# RGB-VIDEO.net
KiCad netlist of a schematic drawn in EAGLE
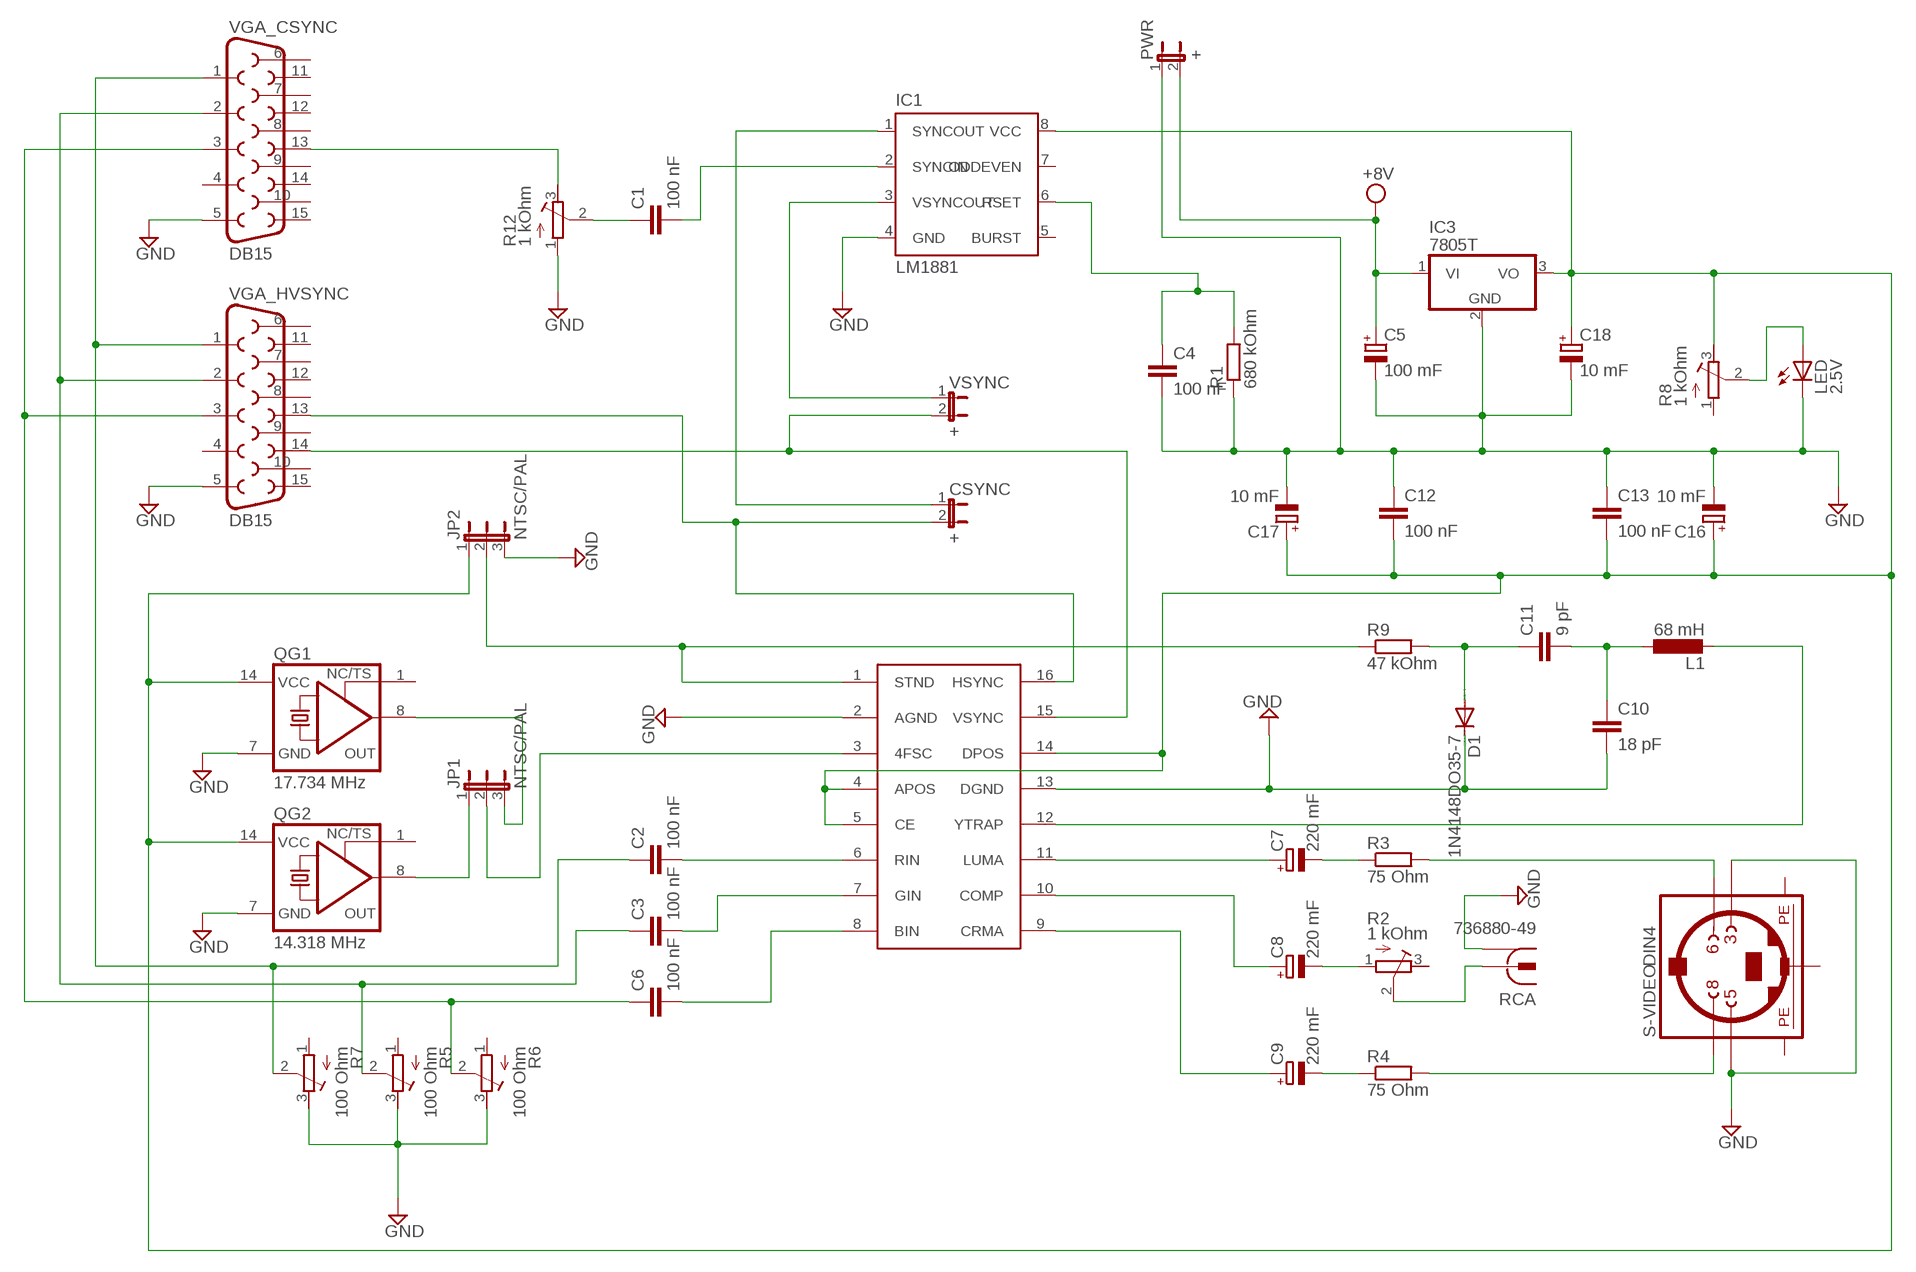
[diagram p0: schematic, sheet 1]

(export (version "E")
  (design (tool "Eeschema 10.0.6"))
  (components
    (comp (ref "C1")
      (value "100 nF")
      (footprint "eagle-import:C050-025X075")
      (libsource (lib "eagle-import") (part "C-EU050-025X075"))
    )
    (comp (ref "C2")
      (value "100 nF")
      (footprint "eagle-import:C050-025X075")
      (libsource (lib "eagle-import") (part "C-EU050-025X075"))
    )
    (comp (ref "C3")
      (value "100 nF")
      (footprint "eagle-import:C050-025X075")
      (libsource (lib "eagle-import") (part "C-EU050-025X075"))
    )
    (comp (ref "C4")
      (value "100 nF")
      (footprint "eagle-import:C050-025X075")
      (libsource (lib "eagle-import") (part "C-EU050-025X075"))
    )
    (comp (ref "C5")
      (value "100 mF")
      (footprint "eagle-import:E3,5-10")
      (libsource (lib "eagle-import") (part "CPOL-EUE3.5-10"))
    )
    (comp (ref "C6")
      (value "100 nF")
      (footprint "eagle-import:C050-025X075")
      (libsource (lib "eagle-import") (part "C-EU050-025X075"))
    )
    (comp (ref "C7")
      (value "220 mF")
      (footprint "eagle-import:E3,5-10")
      (libsource (lib "eagle-import") (part "CPOL-EUE3.5-10"))
    )
    (comp (ref "C8")
      (value "220 mF")
      (footprint "eagle-import:E3,5-10")
      (libsource (lib "eagle-import") (part "CPOL-EUE3.5-10"))
    )
    (comp (ref "C9")
      (value "220 mF")
      (footprint "eagle-import:E3,5-10")
      (libsource (lib "eagle-import") (part "CPOL-EUE3.5-10"))
    )
    (comp (ref "C10")
      (value "18 pF")
      (footprint "eagle-import:C025-024X044")
      (libsource (lib "eagle-import") (part "C-EU025-024X044"))
    )
    (comp (ref "C11")
      (value "9 pF")
      (footprint "eagle-import:C025-024X044")
      (libsource (lib "eagle-import") (part "C-EU025-024X044"))
    )
    (comp (ref "C12")
      (value "100 nF")
      (footprint "eagle-import:C050-025X075")
      (libsource (lib "eagle-import") (part "C-EU050-025X075"))
    )
    (comp (ref "C13")
      (value "100 nF")
      (footprint "eagle-import:C050-025X075")
      (libsource (lib "eagle-import") (part "C-EU050-025X075"))
    )
    (comp (ref "C16")
      (value "10 mF")
      (footprint "eagle-import:E3,5-8")
      (libsource (lib "eagle-import") (part "CPOL-EUE3.5-8"))
    )
    (comp (ref "C17")
      (value "10 mF")
      (footprint "eagle-import:E3,5-8")
      (libsource (lib "eagle-import") (part "CPOL-EUE3.5-8"))
    )
    (comp (ref "C18")
      (value "10 mF")
      (footprint "eagle-import:E3,5-8")
      (libsource (lib "eagle-import") (part "CPOL-EUE3.5-8"))
    )
    (comp (ref "CSYNC")
      (value "+")
      (footprint "eagle-import:JP1")
      (libsource (lib "eagle-import") (part "JP1E"))
    )
    (comp (ref "D1")
      (value "1N4148DO35-7")
      (footprint "eagle-import:DO35-7")
      (libsource (lib "eagle-import") (part "1N4148DO35-7"))
    )
    (comp (ref "IC1")
      (value "LM1881")
      (footprint "eagle-import:DIL08")
      (libsource (lib "eagle-import") (part "LM1881"))
    )
    (comp (ref "IC2")
      (value "AD725")
      (footprint "eagle-import:SO16W")
      (libsource (lib "eagle-import") (part "AD725"))
    )
    (comp (ref "IC3")
      (value "7805T")
      (footprint "eagle-import:TO220H")
      (libsource (lib "eagle-import") (part "78T05"))
    )
    (comp (ref "JP1")
      (value "NTSC/PAL")
      (footprint "eagle-import:JP2")
      (libsource (lib "eagle-import") (part "JP2E"))
    )
    (comp (ref "JP2")
      (value "NTSC/PAL")
      (footprint "eagle-import:JP2")
      (libsource (lib "eagle-import") (part "JP2E"))
    )
    (comp (ref "L1")
      (value "68 mH")
      (footprint "eagle-import:6000-XXXX-RC")
      (libsource (lib "eagle-import") (part "L-EU6000-XXX-RC"))
    )
    (comp (ref "LED")
      (value "2.5V")
      (footprint "eagle-import:LED3MM")
      (libsource (lib "eagle-import") (part "LED3MM"))
    )
    (comp (ref "PWR")
      (value "+")
      (footprint "eagle-import:JP1")
      (libsource (lib "eagle-import") (part "JP1E"))
    )
    (comp (ref "QG1")
      (value "17.734 MHz")
      (footprint "eagle-import:DIL14S")
      (libsource (lib "eagle-import") (part "XO-14"))
    )
    (comp (ref "QG2")
      (value "14.318 MHz")
      (footprint "eagle-import:DIL14S")
      (libsource (lib "eagle-import") (part "XO-14"))
    )
    (comp (ref "R1")
      (value "680 kOhm")
      (footprint "eagle-import:0204_7")
      (libsource (lib "eagle-import") (part "R-EU_0204/7"))
    )
    (comp (ref "R2")
      (value "1 kOhm")
      (footprint "eagle-import:RTRIM3339P")
      (libsource (lib "eagle-import") (part "R-TRIMM3339P"))
    )
    (comp (ref "R3")
      (value "75 Ohm")
      (footprint "eagle-import:0204_7")
      (libsource (lib "eagle-import") (part "R-EU_0204/7"))
    )
    (comp (ref "R4")
      (value "75 Ohm")
      (footprint "eagle-import:0204_7")
      (libsource (lib "eagle-import") (part "R-EU_0204/7"))
    )
    (comp (ref "R5")
      (value "100 Ohm")
      (footprint "eagle-import:RTRIM3339P")
      (libsource (lib "eagle-import") (part "R-TRIMM3339P"))
    )
    (comp (ref "R6")
      (value "100 Ohm")
      (footprint "eagle-import:RTRIM3339P")
      (libsource (lib "eagle-import") (part "R-TRIMM3339P"))
    )
    (comp (ref "R7")
      (value "100 Ohm")
      (footprint "eagle-import:RTRIM3339P")
      (libsource (lib "eagle-import") (part "R-TRIMM3339P"))
    )
    (comp (ref "R8")
      (value "1 kOhm")
      (footprint "eagle-import:RTRIM3339P")
      (libsource (lib "eagle-import") (part "R-TRIMM3339P"))
    )
    (comp (ref "R9")
      (value "47 kOhm")
      (footprint "eagle-import:0204_7")
      (libsource (lib "eagle-import") (part "R-EU_0204/7"))
    )
    (comp (ref "R12")
      (value "1 kOhm")
      (footprint "eagle-import:RTRIM3339P")
      (libsource (lib "eagle-import") (part "R-TRIMM3339P"))
    )
    (comp (ref "RCA")
      (value "736880-49")
      (footprint "eagle-import:736880-49")
      (libsource (lib "eagle-import") (part "736880-49"))
    )
    (comp (ref "S-VIDEO")
      (value "DIN4")
      (footprint "eagle-import:M_DIN4")
      (libsource (lib "eagle-import") (part "MINI_DIN_4"))
    )
    (comp (ref "VGA_CSYNC")
      (value "DB15")
      (footprint "eagle-import:DB15")
      (libsource (lib "eagle-import") (part "DB15"))
    )
    (comp (ref "VGA_HVSYNC")
      (value "DB15")
      (footprint "eagle-import:DB15")
      (libsource (lib "eagle-import") (part "DB15"))
    )
    (comp (ref "VSYNC")
      (value "+")
      (footprint "eagle-import:JP1")
      (libsource (lib "eagle-import") (part "JP1E"))
    )
  )
  (nets
    (net (code "1") (name "+8V") (class "Default")
      (node (ref "C5") (pin "+") (pinfunction "+_+") (pintype "passive"))
      (node (ref "IC3") (pin "1") (pinfunction "VI_1") (pintype "input"))
      (node (ref "PWR") (pin "2") (pinfunction "2_2") (pintype "passive"))
    )
    (net (code "2") (name "/PE1") (class "Default")
      (node (ref "S-VIDEO") (pin "SH1") (pinfunction "PE1_SH1") (pintype "power_in"))
    )
    (net (code "3") (name "/PE2") (class "Default")
      (node (ref "S-VIDEO") (pin "SH2") (pinfunction "PE2_SH2") (pintype "power_in"))
    )
    (net (code "4") (name "/PE3") (class "Default")
      (node (ref "S-VIDEO") (pin "SH3") (pinfunction "PE3_SH3") (pintype "power_in"))
    )
    (net (code "5") (name "GND") (class "Default")
      (node (ref "C10") (pin "2") (pinfunction "2_2") (pintype "passive"))
      (node (ref "C12") (pin "1") (pinfunction "1_1") (pintype "passive"))
      (node (ref "C13") (pin "1") (pinfunction "1_1") (pintype "passive"))
      (node (ref "C16") (pin "-") (pinfunction "-_-") (pintype "passive"))
      (node (ref "C17") (pin "-") (pinfunction "-_-") (pintype "passive"))
      (node (ref "C18") (pin "-") (pinfunction "-_-") (pintype "passive"))
      (node (ref "C4") (pin "2") (pinfunction "2_2") (pintype "passive"))
      (node (ref "C5") (pin "-") (pinfunction "-_-") (pintype "passive"))
      (node (ref "D1") (pin "C") (pinfunction "C_C") (pintype "passive"))
      (node (ref "IC1") (pin "4") (pinfunction "GND_4") (pintype "power_in"))
      (node (ref "IC2") (pin "13") (pinfunction "DGND_13") (pintype "bidirectional"))
      (node (ref "IC2") (pin "2") (pinfunction "AGND_2") (pintype "bidirectional"))
      (node (ref "IC3") (pin "2") (pinfunction "GND_2") (pintype "passive"))
      (node (ref "JP2") (pin "3") (pinfunction "3_3") (pintype "passive"))
      (node (ref "LED") (pin "K") (pinfunction "C_K") (pintype "passive"))
      (node (ref "PWR") (pin "1") (pinfunction "1_1") (pintype "passive"))
      (node (ref "QG1") (pin "7") (pinfunction "GND_7") (pintype "power_in"))
      (node (ref "QG2") (pin "7") (pinfunction "GND_7") (pintype "power_in"))
      (node (ref "R1") (pin "1") (pinfunction "1_1") (pintype "passive"))
      (node (ref "R12") (pin "1") (pinfunction "A_1") (pintype "passive"))
      (node (ref "R5") (pin "3") (pinfunction "E_3") (pintype "passive"))
      (node (ref "R6") (pin "3") (pinfunction "E_3") (pintype "passive"))
      (node (ref "R7") (pin "3") (pinfunction "E_3") (pintype "passive"))
      (node (ref "RCA") (pin "1") (pinfunction "1_1") (pintype "passive"))
      (node (ref "RCA") (pin "1@1") (pinfunction "1_1@1") (pintype "passive"))
      (node (ref "RCA") (pin "1@2") (pinfunction "1_1@2") (pintype "passive"))
      (node (ref "S-VIDEO") (pin "3") (pinfunction "3_3") (pintype "passive"))
      (node (ref "S-VIDEO") (pin "5") (pinfunction "5_5") (pintype "passive"))
      (node (ref "VGA_CSYNC") (pin "5") (pinfunction "5_5") (pintype "passive"))
      (node (ref "VGA_HVSYNC") (pin "5") (pinfunction "5_5") (pintype "passive"))
    )
    (net (code "6") (name "Net-(C7-Pad-)") (class "Default")
      (node (ref "C7") (pin "-") (pinfunction "-_-") (pintype "passive"))
      (node (ref "R3") (pin "1") (pinfunction "1_1") (pintype "passive"))
    )
    (net (code "7") (name "Net-(C9-Pad-)") (class "Default")
      (node (ref "C9") (pin "-") (pinfunction "-_-") (pintype "passive"))
      (node (ref "R4") (pin "1") (pinfunction "1_1") (pintype "passive"))
    )
    (net (code "8") (name "Net-(C10-Pad1)") (class "Default")
      (node (ref "C10") (pin "1") (pinfunction "1_1") (pintype "passive"))
      (node (ref "C11") (pin "2") (pinfunction "2_2") (pintype "passive"))
      (node (ref "L1") (pin "1") (pinfunction "1_1") (pintype "passive"))
    )
    (net (code "9") (name "Net-(C11-Pad1)") (class "Default")
      (node (ref "C11") (pin "1") (pinfunction "1_1") (pintype "passive"))
      (node (ref "D1") (pin "A") (pinfunction "A_A") (pintype "passive"))
      (node (ref "R9") (pin "2") (pinfunction "2_2") (pintype "passive"))
    )
    (net (code "10") (name "Net-(IC1-RSET)") (class "Default")
      (node (ref "C4") (pin "1") (pinfunction "1_1") (pintype "passive"))
      (node (ref "IC1") (pin "6") (pinfunction "RSET_6") (pintype "output"))
      (node (ref "R1") (pin "2") (pinfunction "2_2") (pintype "passive"))
    )
    (net (code "11") (name "Net-(IC1-SYNCIN)") (class "Default")
      (node (ref "C1") (pin "2") (pinfunction "2_2") (pintype "passive"))
      (node (ref "IC1") (pin "2") (pinfunction "SYNCIN_2") (pintype "input"))
    )
    (net (code "12") (name "Net-(IC1-SYNCOUT)") (class "Default")
      (node (ref "CSYNC") (pin "1") (pinfunction "1_1") (pintype "passive"))
      (node (ref "IC1") (pin "1") (pinfunction "SYNCOUT_1") (pintype "output"))
    )
    (net (code "13") (name "Net-(IC1-VCC)") (class "Default")
      (node (ref "C12") (pin "2") (pinfunction "2_2") (pintype "passive"))
      (node (ref "C13") (pin "2") (pinfunction "2_2") (pintype "passive"))
      (node (ref "C16") (pin "+") (pinfunction "+_+") (pintype "passive"))
      (node (ref "C17") (pin "+") (pinfunction "+_+") (pintype "passive"))
      (node (ref "C18") (pin "+") (pinfunction "+_+") (pintype "passive"))
      (node (ref "IC1") (pin "8") (pinfunction "VCC_8") (pintype "power_in"))
      (node (ref "IC2") (pin "14") (pinfunction "DPOS_14") (pintype "bidirectional"))
      (node (ref "IC2") (pin "4") (pinfunction "APOS_4") (pintype "bidirectional"))
      (node (ref "IC2") (pin "5") (pinfunction "CE_5") (pintype "bidirectional"))
      (node (ref "IC3") (pin "3") (pinfunction "VO_3") (pintype "passive"))
      (node (ref "JP2") (pin "1") (pinfunction "1_1") (pintype "passive"))
      (node (ref "QG1") (pin "14") (pinfunction "VCC_14") (pintype "power_in"))
      (node (ref "QG2") (pin "14") (pinfunction "VCC_14") (pintype "power_in"))
      (node (ref "R8") (pin "3") (pinfunction "E_3") (pintype "passive"))
    )
    (net (code "14") (name "Net-(IC1-VSYNCOUT)") (class "Default")
      (node (ref "IC1") (pin "3") (pinfunction "VSYNCOUT_3") (pintype "output"))
      (node (ref "VSYNC") (pin "1") (pinfunction "1_1") (pintype "passive"))
    )
    (net (code "15") (name "Net-(IC2-4FSC)") (class "Default")
      (node (ref "IC2") (pin "3") (pinfunction "4FSC_3") (pintype "bidirectional"))
      (node (ref "JP1") (pin "2") (pinfunction "2_2") (pintype "passive"))
    )
    (net (code "16") (name "Net-(IC2-BIN)") (class "Default")
      (node (ref "C6") (pin "2") (pinfunction "2_2") (pintype "passive"))
      (node (ref "IC2") (pin "8") (pinfunction "BIN_8") (pintype "bidirectional"))
    )
    (net (code "17") (name "Net-(IC2-COMP)") (class "Default")
      (node (ref "C8") (pin "+") (pinfunction "+_+") (pintype "passive"))
      (node (ref "IC2") (pin "10") (pinfunction "COMP_10") (pintype "bidirectional"))
    )
    (net (code "18") (name "Net-(IC2-CRMA)") (class "Default")
      (node (ref "C9") (pin "+") (pinfunction "+_+") (pintype "passive"))
      (node (ref "IC2") (pin "9") (pinfunction "CRMA_9") (pintype "bidirectional"))
    )
    (net (code "19") (name "Net-(IC2-GIN)") (class "Default")
      (node (ref "C3") (pin "2") (pinfunction "2_2") (pintype "passive"))
      (node (ref "IC2") (pin "7") (pinfunction "GIN_7") (pintype "bidirectional"))
    )
    (net (code "20") (name "Net-(IC2-HSYNC)") (class "Default")
      (node (ref "CSYNC") (pin "2") (pinfunction "2_2") (pintype "passive"))
      (node (ref "IC2") (pin "16") (pinfunction "HSYNC_16") (pintype "bidirectional"))
      (node (ref "VGA_HVSYNC") (pin "13") (pinfunction "13_13") (pintype "passive"))
    )
    (net (code "21") (name "Net-(IC2-LUMA)") (class "Default")
      (node (ref "C7") (pin "+") (pinfunction "+_+") (pintype "passive"))
      (node (ref "IC2") (pin "11") (pinfunction "LUMA_11") (pintype "bidirectional"))
    )
    (net (code "22") (name "Net-(IC2-RIN)") (class "Default")
      (node (ref "C2") (pin "2") (pinfunction "2_2") (pintype "passive"))
      (node (ref "IC2") (pin "6") (pinfunction "RIN_6") (pintype "bidirectional"))
    )
    (net (code "23") (name "Net-(IC2-STND)") (class "Default")
      (node (ref "IC2") (pin "1") (pinfunction "STND_1") (pintype "bidirectional"))
      (node (ref "JP2") (pin "2") (pinfunction "2_2") (pintype "passive"))
      (node (ref "R9") (pin "1") (pinfunction "1_1") (pintype "passive"))
    )
    (net (code "24") (name "Net-(IC2-VSYNC)") (class "Default")
      (node (ref "IC2") (pin "15") (pinfunction "VSYNC_15") (pintype "bidirectional"))
      (node (ref "VGA_HVSYNC") (pin "14") (pinfunction "14_14") (pintype "passive"))
      (node (ref "VSYNC") (pin "2") (pinfunction "2_2") (pintype "passive"))
    )
    (net (code "25") (name "Net-(IC2-YTRAP)") (class "Default")
      (node (ref "IC2") (pin "12") (pinfunction "YTRAP_12") (pintype "bidirectional"))
      (node (ref "L1") (pin "2") (pinfunction "2_2") (pintype "passive"))
    )
    (net (code "26") (name "Net-(QG1-OUT)") (class "Default")
      (node (ref "JP1") (pin "3") (pinfunction "3_3") (pintype "passive"))
      (node (ref "QG1") (pin "8") (pinfunction "OUT_8") (pintype "output"))
    )
    (net (code "27") (name "Net-(QG2-OUT)") (class "Default")
      (node (ref "JP1") (pin "1") (pinfunction "1_1") (pintype "passive"))
      (node (ref "QG2") (pin "8") (pinfunction "OUT_8") (pintype "output"))
    )
    (net (code "28") (name "Net-(R2-A)") (class "Default")
      (node (ref "C8") (pin "-") (pinfunction "-_-") (pintype "passive"))
      (node (ref "R2") (pin "1") (pinfunction "A_1") (pintype "passive"))
    )
    (net (code "29") (name "Net-(R2-S)") (class "Default")
      (node (ref "R2") (pin "2") (pinfunction "S_2") (pintype "passive"))
      (node (ref "RCA") (pin "2") (pinfunction "2_2") (pintype "passive"))
    )
    (net (code "30") (name "Net-(R3-Pad2)") (class "Default")
      (node (ref "R3") (pin "2") (pinfunction "2_2") (pintype "passive"))
      (node (ref "S-VIDEO") (pin "6") (pinfunction "6_6") (pintype "passive"))
    )
    (net (code "31") (name "Net-(R4-Pad2)") (class "Default")
      (node (ref "R4") (pin "2") (pinfunction "2_2") (pintype "passive"))
      (node (ref "S-VIDEO") (pin "8") (pinfunction "8_8") (pintype "passive"))
    )
    (net (code "32") (name "Net-(R5-S)") (class "Default")
      (node (ref "C3") (pin "1") (pinfunction "1_1") (pintype "passive"))
      (node (ref "R5") (pin "2") (pinfunction "S_2") (pintype "passive"))
      (node (ref "VGA_CSYNC") (pin "2") (pinfunction "2_2") (pintype "passive"))
      (node (ref "VGA_HVSYNC") (pin "2") (pinfunction "2_2") (pintype "passive"))
    )
    (net (code "33") (name "Net-(R6-S)") (class "Default")
      (node (ref "C6") (pin "1") (pinfunction "1_1") (pintype "passive"))
      (node (ref "R6") (pin "2") (pinfunction "S_2") (pintype "passive"))
      (node (ref "VGA_CSYNC") (pin "3") (pinfunction "3_3") (pintype "passive"))
      (node (ref "VGA_HVSYNC") (pin "3") (pinfunction "3_3") (pintype "passive"))
    )
    (net (code "34") (name "Net-(R7-S)") (class "Default")
      (node (ref "C2") (pin "1") (pinfunction "1_1") (pintype "passive"))
      (node (ref "R7") (pin "2") (pinfunction "S_2") (pintype "passive"))
      (node (ref "VGA_CSYNC") (pin "1") (pinfunction "1_1") (pintype "passive"))
      (node (ref "VGA_HVSYNC") (pin "1") (pinfunction "1_1") (pintype "passive"))
    )
    (net (code "35") (name "Net-(R8-S)") (class "Default")
      (node (ref "LED") (pin "A") (pinfunction "A_A") (pintype "passive"))
      (node (ref "R8") (pin "2") (pinfunction "S_2") (pintype "passive"))
    )
    (net (code "36") (name "Net-(R12-E)") (class "Default")
      (node (ref "R12") (pin "3") (pinfunction "E_3") (pintype "passive"))
      (node (ref "VGA_CSYNC") (pin "13") (pinfunction "13_13") (pintype "passive"))
    )
    (net (code "37") (name "Net-(R12-S)") (class "Default")
      (node (ref "C1") (pin "1") (pinfunction "1_1") (pintype "passive"))
      (node (ref "R12") (pin "2") (pinfunction "S_2") (pintype "passive"))
    )
    (net (code "38") (name "unconnected-(IC1-BURST-Pad5)") (class "Default")
      (node (ref "IC1") (pin "5") (pinfunction "BURST_5") (pintype "output"))
    )
    (net (code "39") (name "unconnected-(IC1-ODDEVEN-Pad7)") (class "Default")
      (node (ref "IC1") (pin "7") (pinfunction "ODDEVEN_7") (pintype "output"))
    )
    (net (code "40") (name "unconnected-(QG1-TS-Pad1)") (class "Default")
      (node (ref "QG1") (pin "1") (pinfunction "TS_1") (pintype "passive"))
    )
    (net (code "41") (name "unconnected-(QG2-TS-Pad1)") (class "Default")
      (node (ref "QG2") (pin "1") (pinfunction "TS_1") (pintype "passive"))
    )
    (net (code "42") (name "unconnected-(R2-E-Pad3)") (class "Default")
      (node (ref "R2") (pin "3") (pinfunction "E_3") (pintype "passive"))
    )
    (net (code "43") (name "unconnected-(R5-A-Pad1)") (class "Default")
      (node (ref "R5") (pin "1") (pinfunction "A_1") (pintype "passive"))
    )
    (net (code "44") (name "unconnected-(R6-A-Pad1)") (class "Default")
      (node (ref "R6") (pin "1") (pinfunction "A_1") (pintype "passive"))
    )
    (net (code "45") (name "unconnected-(R7-A-Pad1)") (class "Default")
      (node (ref "R7") (pin "1") (pinfunction "A_1") (pintype "passive"))
    )
    (net (code "46") (name "unconnected-(R8-A-Pad1)") (class "Default")
      (node (ref "R8") (pin "1") (pinfunction "A_1") (pintype "passive"))
    )
    (net (code "47") (name "unconnected-(VGA_CSYNC-Pad4)") (class "Default")
      (node (ref "VGA_CSYNC") (pin "4") (pinfunction "4_4") (pintype "passive"))
    )
    (net (code "48") (name "unconnected-(VGA_CSYNC-Pad6)") (class "Default")
      (node (ref "VGA_CSYNC") (pin "6") (pinfunction "6_6") (pintype "passive"))
    )
    (net (code "49") (name "unconnected-(VGA_CSYNC-Pad7)") (class "Default")
      (node (ref "VGA_CSYNC") (pin "7") (pinfunction "7_7") (pintype "passive"))
    )
    (net (code "50") (name "unconnected-(VGA_CSYNC-Pad8)") (class "Default")
      (node (ref "VGA_CSYNC") (pin "8") (pinfunction "8_8") (pintype "passive"))
    )
    (net (code "51") (name "unconnected-(VGA_CSYNC-Pad9)") (class "Default")
      (node (ref "VGA_CSYNC") (pin "9") (pinfunction "9_9") (pintype "passive"))
    )
    (net (code "52") (name "unconnected-(VGA_CSYNC-Pad10)") (class "Default")
      (node (ref "VGA_CSYNC") (pin "10") (pinfunction "10_10") (pintype "passive"))
    )
    (net (code "53") (name "unconnected-(VGA_CSYNC-Pad11)") (class "Default")
      (node (ref "VGA_CSYNC") (pin "11") (pinfunction "11_11") (pintype "passive"))
    )
    (net (code "54") (name "unconnected-(VGA_CSYNC-Pad12)") (class "Default")
      (node (ref "VGA_CSYNC") (pin "12") (pinfunction "12_12") (pintype "passive"))
    )
    (net (code "55") (name "unconnected-(VGA_CSYNC-Pad14)") (class "Default")
      (node (ref "VGA_CSYNC") (pin "14") (pinfunction "14_14") (pintype "passive"))
    )
    (net (code "56") (name "unconnected-(VGA_CSYNC-Pad15)") (class "Default")
      (node (ref "VGA_CSYNC") (pin "15") (pinfunction "15_15") (pintype "passive"))
    )
    (net (code "57") (name "unconnected-(VGA_HVSYNC-Pad4)") (class "Default")
      (node (ref "VGA_HVSYNC") (pin "4") (pinfunction "4_4") (pintype "passive"))
    )
    (net (code "58") (name "unconnected-(VGA_HVSYNC-Pad6)") (class "Default")
      (node (ref "VGA_HVSYNC") (pin "6") (pinfunction "6_6") (pintype "passive"))
    )
    (net (code "59") (name "unconnected-(VGA_HVSYNC-Pad7)") (class "Default")
      (node (ref "VGA_HVSYNC") (pin "7") (pinfunction "7_7") (pintype "passive"))
    )
    (net (code "60") (name "unconnected-(VGA_HVSYNC-Pad8)") (class "Default")
      (node (ref "VGA_HVSYNC") (pin "8") (pinfunction "8_8") (pintype "passive"))
    )
    (net (code "61") (name "unconnected-(VGA_HVSYNC-Pad9)") (class "Default")
      (node (ref "VGA_HVSYNC") (pin "9") (pinfunction "9_9") (pintype "passive"))
    )
    (net (code "62") (name "unconnected-(VGA_HVSYNC-Pad10)") (class "Default")
      (node (ref "VGA_HVSYNC") (pin "10") (pinfunction "10_10") (pintype "passive"))
    )
    (net (code "63") (name "unconnected-(VGA_HVSYNC-Pad11)") (class "Default")
      (node (ref "VGA_HVSYNC") (pin "11") (pinfunction "11_11") (pintype "passive"))
    )
    (net (code "64") (name "unconnected-(VGA_HVSYNC-Pad12)") (class "Default")
      (node (ref "VGA_HVSYNC") (pin "12") (pinfunction "12_12") (pintype "passive"))
    )
    (net (code "65") (name "unconnected-(VGA_HVSYNC-Pad15)") (class "Default")
      (node (ref "VGA_HVSYNC") (pin "15") (pinfunction "15_15") (pintype "passive"))
    )
  )
)
